# iobbq_main.net
KiCad netlist of a schematic drawn in EAGLE
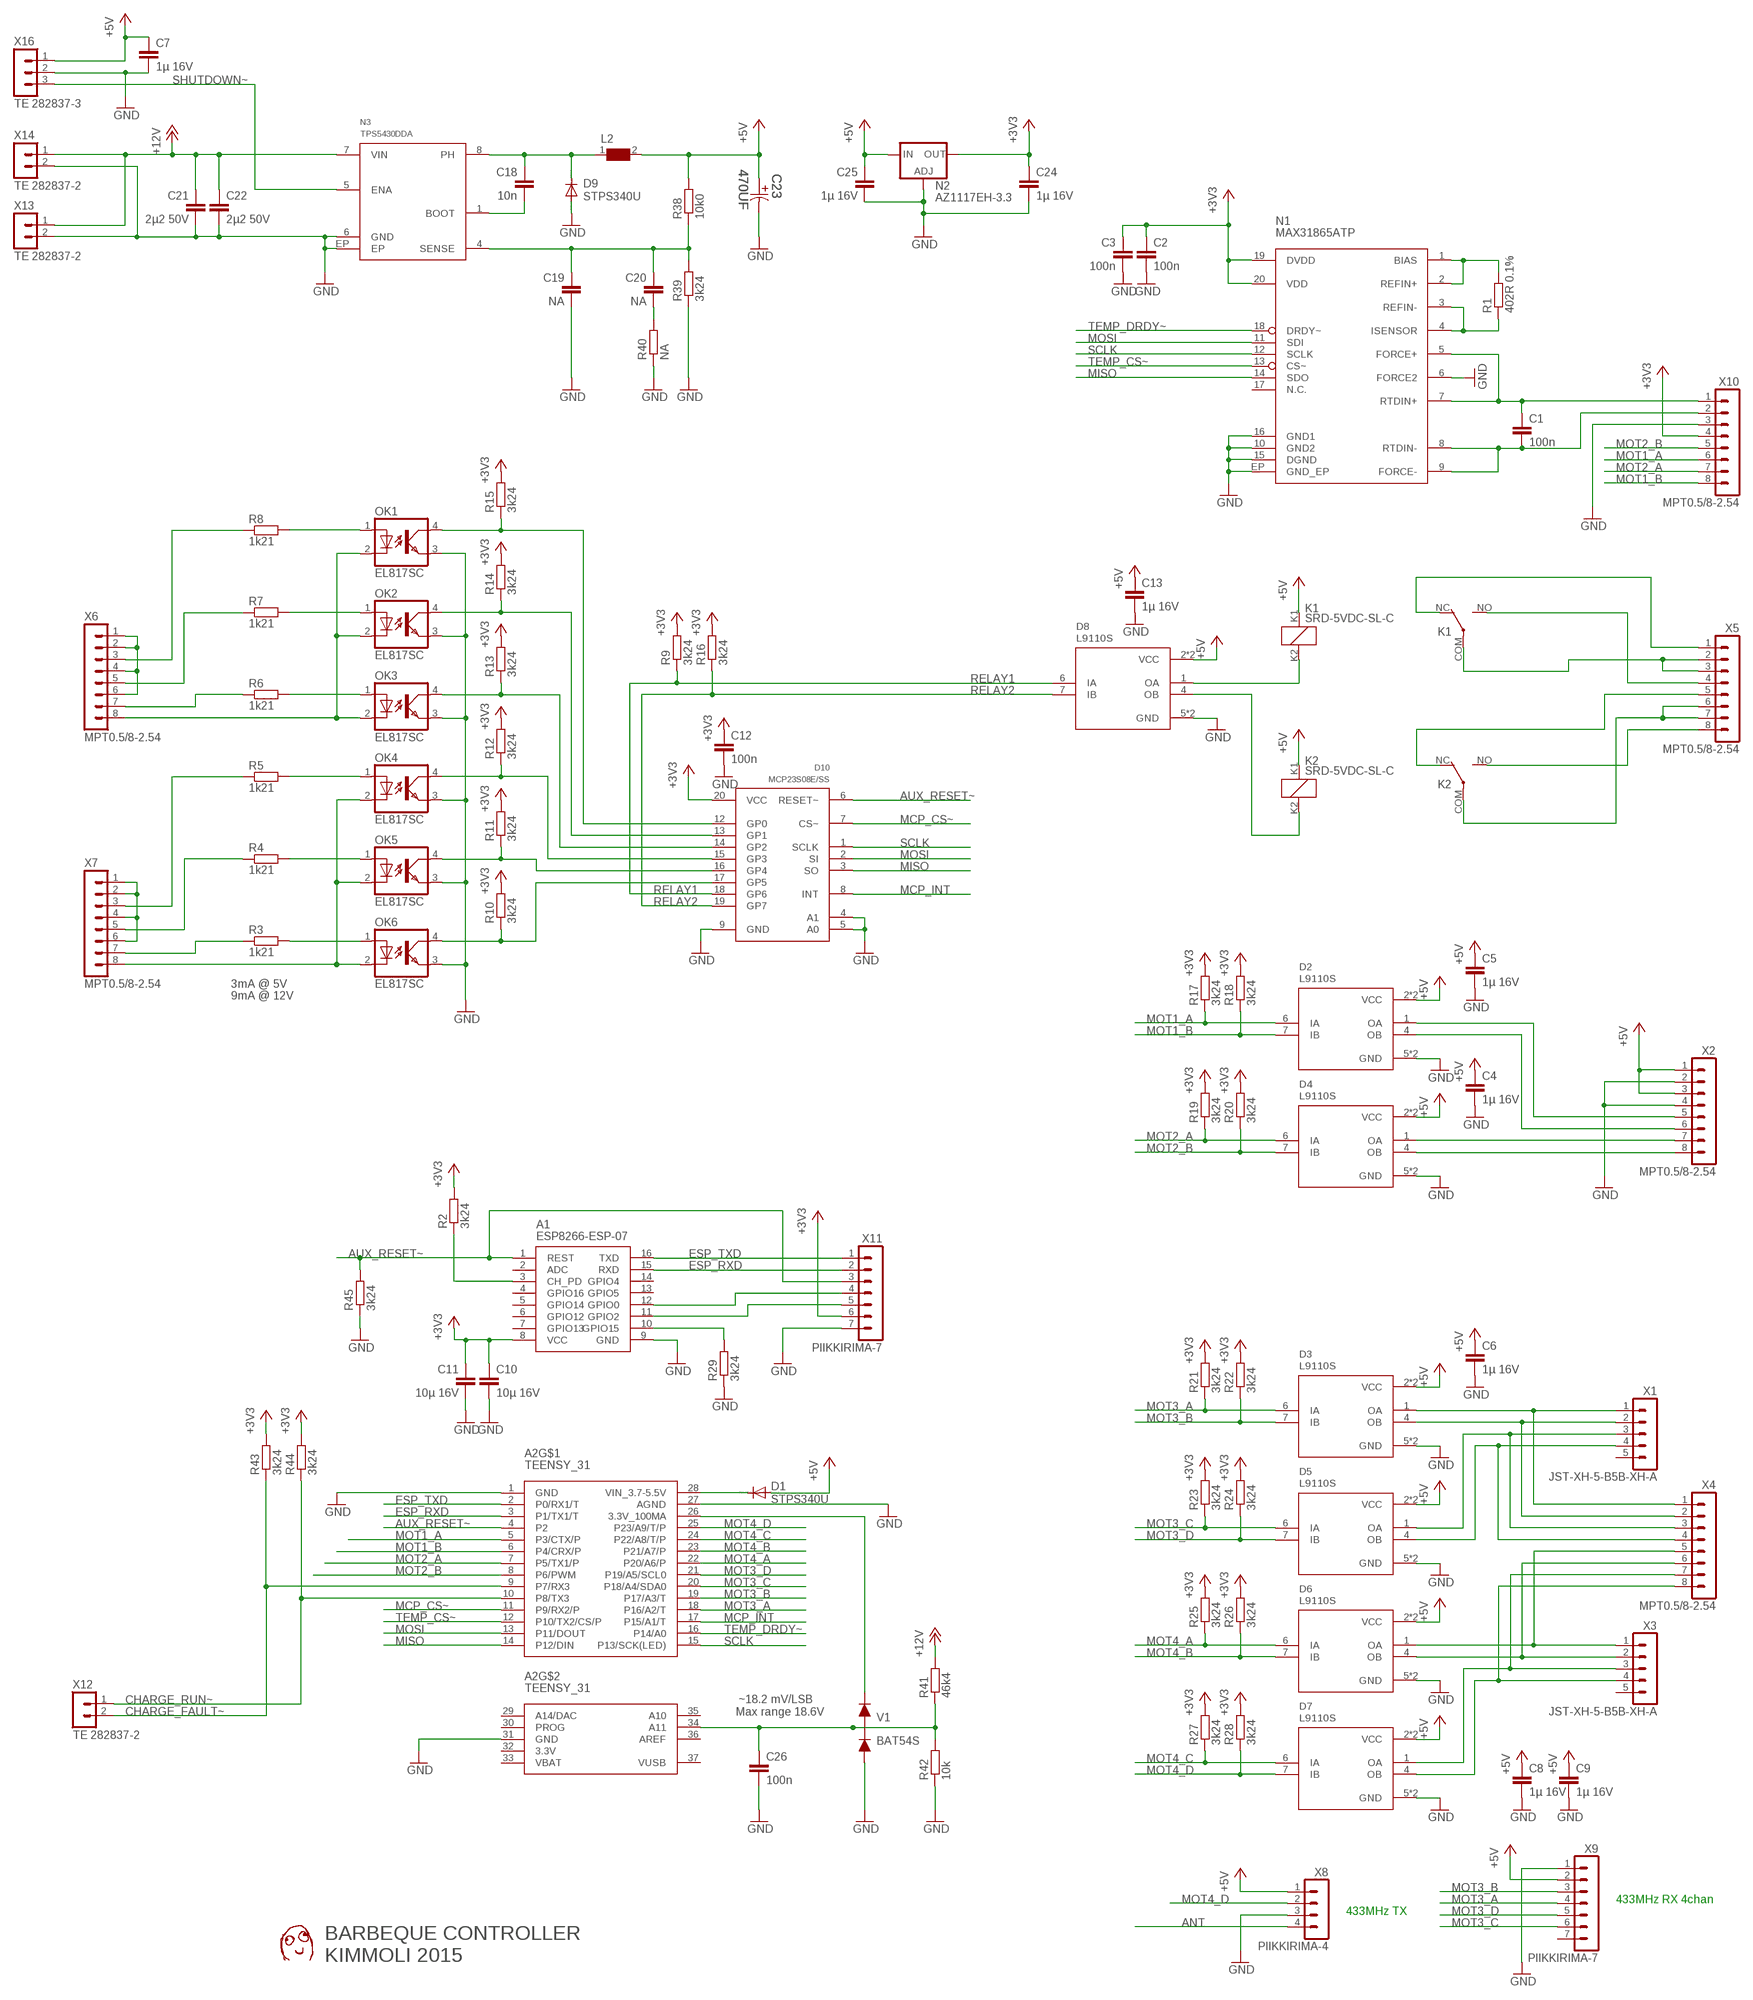
[diagram p0: schematic, sheet 1]

(export (version "E")
  (design (tool "Eeschema 10.0.6"))
  (components
    (comp (ref "A1")
      (value "ESP8266-ESP-07")
      (footprint "eagle-import:ESP8266-ESP-07")
      (libsource (lib "eagle-import") (part "ESP8266-ESP-07"))
    )
    (comp (ref "A2")
      (value "TEENSY_31")
      (footprint "eagle-import:TEENSY_31_THONLY")
      (libsource (lib "eagle-import") (part "TEENSY_31"))
    )
    (comp (ref "C1")
      (value "100n")
      (footprint "eagle-import:C0603")
      (libsource (lib "eagle-import") (part "CAP0603"))
    )
    (comp (ref "C2")
      (value "100n")
      (footprint "eagle-import:C0603")
      (libsource (lib "eagle-import") (part "CAP0603"))
    )
    (comp (ref "C3")
      (value "100n")
      (footprint "eagle-import:C0603")
      (libsource (lib "eagle-import") (part "CAP0603"))
    )
    (comp (ref "C4")
      (value "1µ 16V")
      (footprint "eagle-import:C0805")
      (libsource (lib "eagle-import") (part "CAP0805"))
    )
    (comp (ref "C5")
      (value "1µ 16V")
      (footprint "eagle-import:C0805")
      (libsource (lib "eagle-import") (part "CAP0805"))
    )
    (comp (ref "C6")
      (value "1µ 16V")
      (footprint "eagle-import:C0805")
      (libsource (lib "eagle-import") (part "CAP0805"))
    )
    (comp (ref "C7")
      (value "1µ 16V")
      (footprint "eagle-import:C0805")
      (libsource (lib "eagle-import") (part "CAP0805"))
    )
    (comp (ref "C8")
      (value "1µ 16V")
      (footprint "eagle-import:C0805")
      (libsource (lib "eagle-import") (part "CAP0805"))
    )
    (comp (ref "C9")
      (value "1µ 16V")
      (footprint "eagle-import:C0805")
      (libsource (lib "eagle-import") (part "CAP0805"))
    )
    (comp (ref "C10")
      (value "10µ 16V")
      (footprint "eagle-import:C0805")
      (libsource (lib "eagle-import") (part "CAP0805"))
    )
    (comp (ref "C11")
      (value "10µ 16V")
      (footprint "eagle-import:C0805")
      (libsource (lib "eagle-import") (part "CAP0805"))
    )
    (comp (ref "C12")
      (value "100n")
      (footprint "eagle-import:C0603")
      (libsource (lib "eagle-import") (part "CAP0603"))
    )
    (comp (ref "C13")
      (value "1µ 16V")
      (footprint "eagle-import:C0805")
      (libsource (lib "eagle-import") (part "CAP0805"))
    )
    (comp (ref "C18")
      (value "10n")
      (footprint "eagle-import:C0805")
      (libsource (lib "eagle-import") (part "CAP0805"))
    )
    (comp (ref "C19")
      (value "NA")
      (footprint "eagle-import:C0603")
      (libsource (lib "eagle-import") (part "CAP0603"))
    )
    (comp (ref "C20")
      (value "NA")
      (footprint "eagle-import:C0603")
      (libsource (lib "eagle-import") (part "CAP0603"))
    )
    (comp (ref "C21")
      (value "2µ2 50V")
      (footprint "eagle-import:C0805")
      (libsource (lib "eagle-import") (part "CAP0805"))
    )
    (comp (ref "C22")
      (value "2µ2 50V")
      (footprint "eagle-import:C0805")
      (libsource (lib "eagle-import") (part "CAP0805"))
    )
    (comp (ref "C23")
      (value "470UF")
      (footprint "eagle-import:CAPAE1350X1400N")
      (fields (field (name "MPN") "EEVFK1V471Q") (field (name "TOLERANCE") "±20 %"))
      (libsource (lib "eagle-import") (part "EEV--CASE-H13FK1V471Q"))
    )
    (comp (ref "C24")
      (value "1µ 16V")
      (footprint "eagle-import:C0805")
      (libsource (lib "eagle-import") (part "CAP0805"))
    )
    (comp (ref "C25")
      (value "1µ 16V")
      (footprint "eagle-import:C0805")
      (libsource (lib "eagle-import") (part "CAP0805"))
    )
    (comp (ref "C26")
      (value "100n")
      (footprint "eagle-import:C0603")
      (libsource (lib "eagle-import") (part "CAP0603"))
    )
    (comp (ref "D1")
      (value "STPS340U")
      (footprint "eagle-import:SMB")
      (libsource (lib "eagle-import") (part "DIODE-SMB"))
    )
    (comp (ref "D2")
      (value "L9110S")
      (footprint "eagle-import:SOIC8-N_MC")
      (libsource (lib "eagle-import") (part "L9110S"))
    )
    (comp (ref "D3")
      (value "L9110S")
      (footprint "eagle-import:SOIC8-N_MC")
      (libsource (lib "eagle-import") (part "L9110S"))
    )
    (comp (ref "D4")
      (value "L9110S")
      (footprint "eagle-import:SOIC8-N_MC")
      (libsource (lib "eagle-import") (part "L9110S"))
    )
    (comp (ref "D5")
      (value "L9110S")
      (footprint "eagle-import:SOIC8-N_MC")
      (libsource (lib "eagle-import") (part "L9110S"))
    )
    (comp (ref "D6")
      (value "L9110S")
      (footprint "eagle-import:SOIC8-N_MC")
      (libsource (lib "eagle-import") (part "L9110S"))
    )
    (comp (ref "D7")
      (value "L9110S")
      (footprint "eagle-import:SOIC8-N_MC")
      (libsource (lib "eagle-import") (part "L9110S"))
    )
    (comp (ref "D8")
      (value "L9110S")
      (footprint "eagle-import:SOIC8-N_MC")
      (libsource (lib "eagle-import") (part "L9110S"))
    )
    (comp (ref "D9")
      (value "STPS340U")
      (footprint "eagle-import:SMB")
      (libsource (lib "eagle-import") (part "DIODE-SMB"))
    )
    (comp (ref "D10")
      (value "MCP23S08E/SS")
      (footprint "eagle-import:SSOP-20")
      (libsource (lib "eagle-import") (part "MCP23S08E/SS"))
    )
    (comp (ref "K1")
      (value "SRD-5VDC-SL-C")
      (footprint "eagle-import:SRD-SL-C")
      (libsource (lib "eagle-import") (part "SRD-5VDC-SL-C"))
    )
    (comp (ref "K2")
      (value "SRD-5VDC-SL-C")
      (footprint "eagle-import:SRD-SL-C")
      (libsource (lib "eagle-import") (part "SRD-5VDC-SL-C"))
    )
    (comp (ref "L2")
      (value "WE-PD-7447709220_1260/1245/1280/1210")
      (footprint "eagle-import:WE-PD_1260_1245_1280_1210")
      (fields (field (name "MPN") "7447709220"))
      (libsource (lib "eagle-import") (part "WE-PD_1260/1245/1280/1210-7447709220"))
    )
    (comp (ref "N1")
      (value "MAX31865ATP")
      (footprint "eagle-import:TQFN-20")
      (libsource (lib "eagle-import") (part "MAX31865ATP"))
    )
    (comp (ref "N2")
      (value "AZ1117EH-3.3")
      (footprint "eagle-import:SOT223")
      (libsource (lib "eagle-import") (part "LD117A?S33TR"))
    )
    (comp (ref "N3")
      (value "TPS5430DDA")
      (footprint "eagle-import:SOIC8-N-EP")
      (libsource (lib "eagle-import") (part "TPS5430DDA"))
    )
    (comp (ref "OK1")
      (value "EL817SC")
      (footprint "eagle-import:SMD4-7")
      (fields (field (name "MF") "VISHAY/TELEFUNKEN") (field (name "MPN") "SFH6186-2"))
      (libsource (lib "eagle-import") (part "SFH618?6-2"))
    )
    (comp (ref "OK2")
      (value "EL817SC")
      (footprint "eagle-import:SMD4-7")
      (fields (field (name "MF") "VISHAY/TELEFUNKEN") (field (name "MPN") "SFH6186-2"))
      (libsource (lib "eagle-import") (part "SFH618?6-2"))
    )
    (comp (ref "OK3")
      (value "EL817SC")
      (footprint "eagle-import:SMD4-7")
      (fields (field (name "MF") "VISHAY/TELEFUNKEN") (field (name "MPN") "SFH6186-2"))
      (libsource (lib "eagle-import") (part "SFH618?6-2"))
    )
    (comp (ref "OK4")
      (value "EL817SC")
      (footprint "eagle-import:SMD4-7")
      (fields (field (name "MF") "VISHAY/TELEFUNKEN") (field (name "MPN") "SFH6186-2"))
      (libsource (lib "eagle-import") (part "SFH618?6-2"))
    )
    (comp (ref "OK5")
      (value "EL817SC")
      (footprint "eagle-import:SMD4-7")
      (fields (field (name "MF") "VISHAY/TELEFUNKEN") (field (name "MPN") "SFH6186-2"))
      (libsource (lib "eagle-import") (part "SFH618?6-2"))
    )
    (comp (ref "OK6")
      (value "EL817SC")
      (footprint "eagle-import:SMD4-7")
      (fields (field (name "MF") "VISHAY/TELEFUNKEN") (field (name "MPN") "SFH6186-2"))
      (libsource (lib "eagle-import") (part "SFH618?6-2"))
    )
    (comp (ref "R1")
      (value "402R 0.1%")
      (footprint "eagle-import:R0603")
      (libsource (lib "eagle-import") (part "RES0603"))
    )
    (comp (ref "R2")
      (value "3k24")
      (footprint "eagle-import:R0603")
      (libsource (lib "eagle-import") (part "RES0603"))
    )
    (comp (ref "R3")
      (value "1k21")
      (footprint "eagle-import:R0805")
      (libsource (lib "eagle-import") (part "RES0805"))
    )
    (comp (ref "R4")
      (value "1k21")
      (footprint "eagle-import:R0805")
      (libsource (lib "eagle-import") (part "RES0805"))
    )
    (comp (ref "R5")
      (value "1k21")
      (footprint "eagle-import:R0805")
      (libsource (lib "eagle-import") (part "RES0805"))
    )
    (comp (ref "R6")
      (value "1k21")
      (footprint "eagle-import:R0805")
      (libsource (lib "eagle-import") (part "RES0805"))
    )
    (comp (ref "R7")
      (value "1k21")
      (footprint "eagle-import:R0805")
      (libsource (lib "eagle-import") (part "RES0805"))
    )
    (comp (ref "R8")
      (value "1k21")
      (footprint "eagle-import:R0805")
      (libsource (lib "eagle-import") (part "RES0805"))
    )
    (comp (ref "R9")
      (value "3k24")
      (footprint "eagle-import:R0603")
      (libsource (lib "eagle-import") (part "RES0603"))
    )
    (comp (ref "R10")
      (value "3k24")
      (footprint "eagle-import:R0603")
      (libsource (lib "eagle-import") (part "RES0603"))
    )
    (comp (ref "R11")
      (value "3k24")
      (footprint "eagle-import:R0603")
      (libsource (lib "eagle-import") (part "RES0603"))
    )
    (comp (ref "R12")
      (value "3k24")
      (footprint "eagle-import:R0603")
      (libsource (lib "eagle-import") (part "RES0603"))
    )
    (comp (ref "R13")
      (value "3k24")
      (footprint "eagle-import:R0603")
      (libsource (lib "eagle-import") (part "RES0603"))
    )
    (comp (ref "R14")
      (value "3k24")
      (footprint "eagle-import:R0603")
      (libsource (lib "eagle-import") (part "RES0603"))
    )
    (comp (ref "R15")
      (value "3k24")
      (footprint "eagle-import:R0603")
      (libsource (lib "eagle-import") (part "RES0603"))
    )
    (comp (ref "R16")
      (value "3k24")
      (footprint "eagle-import:R0603")
      (libsource (lib "eagle-import") (part "RES0603"))
    )
    (comp (ref "R17")
      (value "3k24")
      (footprint "eagle-import:R0603")
      (libsource (lib "eagle-import") (part "RES0603"))
    )
    (comp (ref "R18")
      (value "3k24")
      (footprint "eagle-import:R0603")
      (libsource (lib "eagle-import") (part "RES0603"))
    )
    (comp (ref "R19")
      (value "3k24")
      (footprint "eagle-import:R0603")
      (libsource (lib "eagle-import") (part "RES0603"))
    )
    (comp (ref "R20")
      (value "3k24")
      (footprint "eagle-import:R0603")
      (libsource (lib "eagle-import") (part "RES0603"))
    )
    (comp (ref "R21")
      (value "3k24")
      (footprint "eagle-import:R0603")
      (libsource (lib "eagle-import") (part "RES0603"))
    )
    (comp (ref "R22")
      (value "3k24")
      (footprint "eagle-import:R0603")
      (libsource (lib "eagle-import") (part "RES0603"))
    )
    (comp (ref "R23")
      (value "3k24")
      (footprint "eagle-import:R0603")
      (libsource (lib "eagle-import") (part "RES0603"))
    )
    (comp (ref "R24")
      (value "3k24")
      (footprint "eagle-import:R0603")
      (libsource (lib "eagle-import") (part "RES0603"))
    )
    (comp (ref "R25")
      (value "3k24")
      (footprint "eagle-import:R0603")
      (libsource (lib "eagle-import") (part "RES0603"))
    )
    (comp (ref "R26")
      (value "3k24")
      (footprint "eagle-import:R0603")
      (libsource (lib "eagle-import") (part "RES0603"))
    )
    (comp (ref "R27")
      (value "3k24")
      (footprint "eagle-import:R0603")
      (libsource (lib "eagle-import") (part "RES0603"))
    )
    (comp (ref "R28")
      (value "3k24")
      (footprint "eagle-import:R0603")
      (libsource (lib "eagle-import") (part "RES0603"))
    )
    (comp (ref "R29")
      (value "3k24")
      (footprint "eagle-import:R0603")
      (libsource (lib "eagle-import") (part "RES0603"))
    )
    (comp (ref "R38")
      (value "10k0")
      (footprint "eagle-import:R0603")
      (libsource (lib "eagle-import") (part "RES0603"))
    )
    (comp (ref "R39")
      (value "3k24")
      (footprint "eagle-import:R0603")
      (libsource (lib "eagle-import") (part "RES0603"))
    )
    (comp (ref "R40")
      (value "NA")
      (footprint "eagle-import:R0603")
      (libsource (lib "eagle-import") (part "RES0603"))
    )
    (comp (ref "R41")
      (value "46k4")
      (footprint "eagle-import:R0603")
      (libsource (lib "eagle-import") (part "RES0603"))
    )
    (comp (ref "R42")
      (value "10k")
      (footprint "eagle-import:R0603")
      (libsource (lib "eagle-import") (part "RES0603"))
    )
    (comp (ref "R43")
      (value "3k24")
      (footprint "eagle-import:R0603")
      (libsource (lib "eagle-import") (part "RES0603"))
    )
    (comp (ref "R44")
      (value "3k24")
      (footprint "eagle-import:R0603")
      (libsource (lib "eagle-import") (part "RES0603"))
    )
    (comp (ref "R45")
      (value "3k24")
      (footprint "eagle-import:R0603")
      (libsource (lib "eagle-import") (part "RES0603"))
    )
    (comp (ref "U$3")
      (value "DAFUG")
      (footprint "eagle-import:DAFUG")
      (libsource (lib "eagle-import") (part "DAFUG"))
    )
    (comp (ref "V1")
      (value "BAT54S")
      (footprint "eagle-import:SOT23")
      (libsource (lib "eagle-import") (part "BAT54S"))
    )
    (comp (ref "X1")
      (value "JST-XH-5-B5B-XH-A")
      (footprint "eagle-import:JST-XH-5")
      (libsource (lib "eagle-import") (part "JST-XH-5-B5B-XH-A"))
    )
    (comp (ref "X2")
      (value "MPT0.5/8-2.54")
      (footprint "eagle-import:MPT0.5_8-2.54")
      (libsource (lib "eagle-import") (part "MPT0.5/8-2.54"))
    )
    (comp (ref "X3")
      (value "JST-XH-5-B5B-XH-A")
      (footprint "eagle-import:JST-XH-5")
      (libsource (lib "eagle-import") (part "JST-XH-5-B5B-XH-A"))
    )
    (comp (ref "X4")
      (value "MPT0.5/8-2.54")
      (footprint "eagle-import:MPT0.5_8-2.54")
      (libsource (lib "eagle-import") (part "MPT0.5/8-2.54"))
    )
    (comp (ref "X5")
      (value "MPT0.5/8-2.54")
      (footprint "eagle-import:MPT0.5_8-2.54")
      (libsource (lib "eagle-import") (part "MPT0.5/8-2.54"))
    )
    (comp (ref "X6")
      (value "MPT0.5/8-2.54")
      (footprint "eagle-import:MPT0.5_8-2.54")
      (libsource (lib "eagle-import") (part "MPT0.5/8-2.54"))
    )
    (comp (ref "X7")
      (value "MPT0.5/8-2.54")
      (footprint "eagle-import:MPT0.5_8-2.54")
      (libsource (lib "eagle-import") (part "MPT0.5/8-2.54"))
    )
    (comp (ref "X8")
      (value "PIIKKIRIMA-4")
      (footprint "eagle-import:PIIKKIRIMA-4")
      (libsource (lib "eagle-import") (part "PIIKKIRIMA-4"))
    )
    (comp (ref "X9")
      (value "PIIKKIRIMA-7")
      (footprint "eagle-import:PIIKKIRIMA-7")
      (libsource (lib "eagle-import") (part "PIIKKIRIMA-7"))
    )
    (comp (ref "X10")
      (value "MPT0.5/8-2.54")
      (footprint "eagle-import:MPT0.5_8-2.54")
      (libsource (lib "eagle-import") (part "MPT0.5/8-2.54"))
    )
    (comp (ref "X11")
      (value "PIIKKIRIMA-7")
      (footprint "eagle-import:PIIKKIRIMA-7")
      (libsource (lib "eagle-import") (part "PIIKKIRIMA-7"))
    )
    (comp (ref "X12")
      (value "TE 282837-2")
      (footprint "eagle-import:TE_RUUVILIITIN2")
      (libsource (lib "eagle-import") (part "TE_RUUVILIITIN2"))
    )
    (comp (ref "X13")
      (value "TE 282837-2")
      (footprint "eagle-import:TE_RUUVILIITIN2")
      (libsource (lib "eagle-import") (part "TE_RUUVILIITIN2"))
    )
    (comp (ref "X14")
      (value "TE 282837-2")
      (footprint "eagle-import:TE_RUUVILIITIN2")
      (libsource (lib "eagle-import") (part "TE_RUUVILIITIN2"))
    )
    (comp (ref "X16")
      (value "TE 282837-3")
      (footprint "eagle-import:TE_RUUVILIITIN3")
      (libsource (lib "eagle-import") (part "TE_RUUVILIITIN3"))
    )
  )
  (nets
    (net (code "1") (name "+3V3") (class "Default")
      (node (ref "A1") (pin "8") (pinfunction "VCC_8") (pintype "bidirectional"))
      (node (ref "C10") (pin "1") (pinfunction "1_1") (pintype "passive"))
      (node (ref "C11") (pin "1") (pinfunction "1_1") (pintype "passive"))
      (node (ref "C12") (pin "1") (pinfunction "1_1") (pintype "passive"))
      (node (ref "C2") (pin "1") (pinfunction "1_1") (pintype "passive"))
      (node (ref "C24") (pin "1") (pinfunction "1_1") (pintype "passive"))
      (node (ref "C3") (pin "1") (pinfunction "1_1") (pintype "passive"))
      (node (ref "D10") (pin "20") (pinfunction "VCC_20") (pintype "bidirectional"))
      (node (ref "N1") (pin "19") (pinfunction "DVDD_19") (pintype "bidirectional"))
      (node (ref "N1") (pin "20") (pinfunction "VDD_20") (pintype "bidirectional"))
      (node (ref "N2") (pin "4") (pinfunction "OUT_4") (pintype "passive"))
      (node (ref "R10") (pin "2") (pinfunction "2_2") (pintype "passive"))
      (node (ref "R11") (pin "2") (pinfunction "2_2") (pintype "passive"))
      (node (ref "R12") (pin "2") (pinfunction "2_2") (pintype "passive"))
      (node (ref "R13") (pin "2") (pinfunction "2_2") (pintype "passive"))
      (node (ref "R14") (pin "2") (pinfunction "2_2") (pintype "passive"))
      (node (ref "R15") (pin "2") (pinfunction "2_2") (pintype "passive"))
      (node (ref "R16") (pin "2") (pinfunction "2_2") (pintype "passive"))
      (node (ref "R17") (pin "2") (pinfunction "2_2") (pintype "passive"))
      (node (ref "R18") (pin "2") (pinfunction "2_2") (pintype "passive"))
      (node (ref "R19") (pin "2") (pinfunction "2_2") (pintype "passive"))
      (node (ref "R2") (pin "2") (pinfunction "2_2") (pintype "passive"))
      (node (ref "R20") (pin "2") (pinfunction "2_2") (pintype "passive"))
      (node (ref "R21") (pin "2") (pinfunction "2_2") (pintype "passive"))
      (node (ref "R22") (pin "2") (pinfunction "2_2") (pintype "passive"))
      (node (ref "R23") (pin "2") (pinfunction "2_2") (pintype "passive"))
      (node (ref "R24") (pin "2") (pinfunction "2_2") (pintype "passive"))
      (node (ref "R25") (pin "2") (pinfunction "2_2") (pintype "passive"))
      (node (ref "R26") (pin "2") (pinfunction "2_2") (pintype "passive"))
      (node (ref "R27") (pin "2") (pinfunction "2_2") (pintype "passive"))
      (node (ref "R28") (pin "2") (pinfunction "2_2") (pintype "passive"))
      (node (ref "R43") (pin "2") (pinfunction "2_2") (pintype "passive"))
      (node (ref "R44") (pin "2") (pinfunction "2_2") (pintype "passive"))
      (node (ref "R9") (pin "2") (pinfunction "2_2") (pintype "passive"))
      (node (ref "X10") (pin "4") (pinfunction "4_4") (pintype "passive"))
      (node (ref "X11") (pin "6") (pinfunction "6_6") (pintype "passive"))
    )
    (net (code "2") (name "+5V") (class "Default")
      (node (ref "C13") (pin "1") (pinfunction "1_1") (pintype "passive"))
      (node (ref "C23") (pin "1") (pinfunction "1_1") (pintype "passive"))
      (node (ref "C25") (pin "1") (pinfunction "1_1") (pintype "passive"))
      (node (ref "C4") (pin "1") (pinfunction "1_1") (pintype "passive"))
      (node (ref "C5") (pin "1") (pinfunction "1_1") (pintype "passive"))
      (node (ref "C6") (pin "1") (pinfunction "1_1") (pintype "passive"))
      (node (ref "C7") (pin "1") (pinfunction "1_1") (pintype "passive"))
      (node (ref "C8") (pin "1") (pinfunction "1_1") (pintype "passive"))
      (node (ref "C9") (pin "1") (pinfunction "1_1") (pintype "passive"))
      (node (ref "D1") (pin "A") (pinfunction "A_A") (pintype "passive"))
      (node (ref "D2") (pin "2") (pinfunction "VCC_2") (pintype "bidirectional"))
      (node (ref "D2") (pin "3") (pinfunction "VCC_3") (pintype "bidirectional"))
      (node (ref "D3") (pin "2") (pinfunction "VCC_2") (pintype "bidirectional"))
      (node (ref "D3") (pin "3") (pinfunction "VCC_3") (pintype "bidirectional"))
      (node (ref "D4") (pin "2") (pinfunction "VCC_2") (pintype "bidirectional"))
      (node (ref "D4") (pin "3") (pinfunction "VCC_3") (pintype "bidirectional"))
      (node (ref "D5") (pin "2") (pinfunction "VCC_2") (pintype "bidirectional"))
      (node (ref "D5") (pin "3") (pinfunction "VCC_3") (pintype "bidirectional"))
      (node (ref "D6") (pin "2") (pinfunction "VCC_2") (pintype "bidirectional"))
      (node (ref "D6") (pin "3") (pinfunction "VCC_3") (pintype "bidirectional"))
      (node (ref "D7") (pin "2") (pinfunction "VCC_2") (pintype "bidirectional"))
      (node (ref "D7") (pin "3") (pinfunction "VCC_3") (pintype "bidirectional"))
      (node (ref "D8") (pin "2") (pinfunction "VCC_2") (pintype "bidirectional"))
      (node (ref "D8") (pin "3") (pinfunction "VCC_3") (pintype "bidirectional"))
      (node (ref "K1") (pin "K1") (pinfunction "1_K1") (pintype "passive"))
      (node (ref "K2") (pin "K1") (pinfunction "1_K1") (pintype "passive"))
      (node (ref "L2") (pin "2") (pinfunction "2_2") (pintype "passive"))
      (node (ref "N2") (pin "3") (pinfunction "IN_3") (pintype "input"))
      (node (ref "R38") (pin "2") (pinfunction "2_2") (pintype "passive"))
      (node (ref "X16") (pin "1") (pinfunction "1_1") (pintype "passive"))
      (node (ref "X2") (pin "1") (pinfunction "1_1") (pintype "passive"))
      (node (ref "X2") (pin "3") (pinfunction "3_3") (pintype "passive"))
      (node (ref "X8") (pin "1") (pinfunction "1_1") (pintype "passive"))
      (node (ref "X9") (pin "2") (pinfunction "2_2") (pintype "passive"))
    )
    (net (code "3") (name "+12V") (class "Default")
      (node (ref "C21") (pin "1") (pinfunction "1_1") (pintype "passive"))
      (node (ref "C22") (pin "1") (pinfunction "1_1") (pintype "passive"))
      (node (ref "N3") (pin "7") (pinfunction "VIN_7") (pintype "bidirectional"))
      (node (ref "R41") (pin "2") (pinfunction "2_2") (pintype "passive"))
      (node (ref "X13") (pin "1") (pinfunction "1_1") (pintype "passive"))
      (node (ref "X14") (pin "1") (pinfunction "1_1") (pintype "passive"))
    )
    (net (code "4") (name "/ANT") (class "Default")
      (node (ref "X8") (pin "4") (pinfunction "4_4") (pintype "passive"))
    )
    (net (code "5") (name "/AUX_RESET~{}") (class "Default")
      (node (ref "A1") (pin "1") (pinfunction "REST_1") (pintype "bidirectional"))
      (node (ref "A2") (pin "4") (pinfunction "P2_4") (pintype "bidirectional"))
      (node (ref "D10") (pin "6") (pinfunction "RESET~{}_6") (pintype "bidirectional"))
      (node (ref "R45") (pin "2") (pinfunction "2_2") (pintype "passive"))
      (node (ref "X11") (pin "3") (pinfunction "3_3") (pintype "passive"))
    )
    (net (code "6") (name "/CHARGE_FAULT~{}") (class "Default")
      (node (ref "A2") (pin "9") (pinfunction "P7/RX3_9") (pintype "bidirectional"))
      (node (ref "R43") (pin "1") (pinfunction "1_1") (pintype "passive"))
      (node (ref "X12") (pin "2") (pinfunction "2_2") (pintype "passive"))
    )
    (net (code "7") (name "/CHARGE_RUN~{}") (class "Default")
      (node (ref "A2") (pin "10") (pinfunction "P8/TX3_10") (pintype "bidirectional"))
      (node (ref "R44") (pin "1") (pinfunction "1_1") (pintype "passive"))
      (node (ref "X12") (pin "1") (pinfunction "1_1") (pintype "passive"))
    )
    (net (code "8") (name "/ESP_RXD") (class "Default")
      (node (ref "A1") (pin "15") (pinfunction "RXD_15") (pintype "bidirectional"))
      (node (ref "A2") (pin "3") (pinfunction "P1/TX1/T_3") (pintype "bidirectional"))
      (node (ref "X11") (pin "2") (pinfunction "2_2") (pintype "passive"))
    )
    (net (code "9") (name "/ESP_TXD") (class "Default")
      (node (ref "A1") (pin "16") (pinfunction "TXD_16") (pintype "bidirectional"))
      (node (ref "A2") (pin "2") (pinfunction "P0/RX1/T_2") (pintype "bidirectional"))
      (node (ref "X11") (pin "1") (pinfunction "1_1") (pintype "passive"))
    )
    (net (code "10") (name "/MCP_CS~{}") (class "Default")
      (node (ref "A2") (pin "11") (pinfunction "P9/RX2/P_11") (pintype "bidirectional"))
      (node (ref "D10") (pin "7") (pinfunction "CS~{}_7") (pintype "bidirectional"))
    )
    (net (code "11") (name "/MCP_INT") (class "Default")
      (node (ref "A2") (pin "17") (pinfunction "P15/A1/T_17") (pintype "bidirectional"))
      (node (ref "D10") (pin "8") (pinfunction "INT_8") (pintype "bidirectional"))
    )
    (net (code "12") (name "/MISO") (class "Default")
      (node (ref "A2") (pin "14") (pinfunction "P12/DIN_14") (pintype "bidirectional"))
      (node (ref "D10") (pin "3") (pinfunction "SO_3") (pintype "bidirectional"))
      (node (ref "N1") (pin "14") (pinfunction "SDO_14") (pintype "bidirectional"))
    )
    (net (code "13") (name "/MOSI") (class "Default")
      (node (ref "A2") (pin "13") (pinfunction "P11/DOUT_13") (pintype "bidirectional"))
      (node (ref "D10") (pin "2") (pinfunction "SI_2") (pintype "bidirectional"))
      (node (ref "N1") (pin "11") (pinfunction "SDI_11") (pintype "bidirectional"))
    )
    (net (code "14") (name "/MOT1_A") (class "Default")
      (node (ref "A2") (pin "5") (pinfunction "P3/CTX/P_5") (pintype "bidirectional"))
      (node (ref "D2") (pin "6") (pinfunction "IA_6") (pintype "bidirectional"))
      (node (ref "R17") (pin "1") (pinfunction "1_1") (pintype "passive"))
      (node (ref "X10") (pin "6") (pinfunction "6_6") (pintype "passive"))
    )
    (net (code "15") (name "/MOT1_B") (class "Default")
      (node (ref "A2") (pin "6") (pinfunction "P4/CRX/P_6") (pintype "bidirectional"))
      (node (ref "D2") (pin "7") (pinfunction "IB_7") (pintype "bidirectional"))
      (node (ref "R18") (pin "1") (pinfunction "1_1") (pintype "passive"))
      (node (ref "X10") (pin "8") (pinfunction "8_8") (pintype "passive"))
    )
    (net (code "16") (name "/MOT2_A") (class "Default")
      (node (ref "A2") (pin "7") (pinfunction "P5/TX1/P_7") (pintype "bidirectional"))
      (node (ref "D4") (pin "6") (pinfunction "IA_6") (pintype "bidirectional"))
      (node (ref "R19") (pin "1") (pinfunction "1_1") (pintype "passive"))
      (node (ref "X10") (pin "7") (pinfunction "7_7") (pintype "passive"))
    )
    (net (code "17") (name "/MOT2_B") (class "Default")
      (node (ref "A2") (pin "8") (pinfunction "P6/PWM_8") (pintype "bidirectional"))
      (node (ref "D4") (pin "7") (pinfunction "IB_7") (pintype "bidirectional"))
      (node (ref "R20") (pin "1") (pinfunction "1_1") (pintype "passive"))
      (node (ref "X10") (pin "5") (pinfunction "5_5") (pintype "passive"))
    )
    (net (code "18") (name "/MOT3_A") (class "Default")
      (node (ref "A2") (pin "18") (pinfunction "P16/A2/T_18") (pintype "bidirectional"))
      (node (ref "D3") (pin "6") (pinfunction "IA_6") (pintype "bidirectional"))
      (node (ref "R21") (pin "1") (pinfunction "1_1") (pintype "passive"))
      (node (ref "X9") (pin "4") (pinfunction "4_4") (pintype "passive"))
    )
    (net (code "19") (name "/MOT3_B") (class "Default")
      (node (ref "A2") (pin "19") (pinfunction "P17/A3/T_19") (pintype "bidirectional"))
      (node (ref "D3") (pin "7") (pinfunction "IB_7") (pintype "bidirectional"))
      (node (ref "R22") (pin "1") (pinfunction "1_1") (pintype "passive"))
      (node (ref "X9") (pin "3") (pinfunction "3_3") (pintype "passive"))
    )
    (net (code "20") (name "/MOT3_C") (class "Default")
      (node (ref "A2") (pin "20") (pinfunction "P18/A4/SDA0_20") (pintype "bidirectional"))
      (node (ref "D5") (pin "6") (pinfunction "IA_6") (pintype "bidirectional"))
      (node (ref "R23") (pin "1") (pinfunction "1_1") (pintype "passive"))
      (node (ref "X9") (pin "6") (pinfunction "6_6") (pintype "passive"))
    )
    (net (code "21") (name "/MOT3_D") (class "Default")
      (node (ref "A2") (pin "21") (pinfunction "P19/A5/SCL0_21") (pintype "bidirectional"))
      (node (ref "D5") (pin "7") (pinfunction "IB_7") (pintype "bidirectional"))
      (node (ref "R24") (pin "1") (pinfunction "1_1") (pintype "passive"))
      (node (ref "X9") (pin "5") (pinfunction "5_5") (pintype "passive"))
    )
    (net (code "22") (name "/MOT4_A") (class "Default")
      (node (ref "A2") (pin "22") (pinfunction "P20/A6/P_22") (pintype "bidirectional"))
      (node (ref "D6") (pin "6") (pinfunction "IA_6") (pintype "bidirectional"))
      (node (ref "R25") (pin "1") (pinfunction "1_1") (pintype "passive"))
    )
    (net (code "23") (name "/MOT4_B") (class "Default")
      (node (ref "A2") (pin "23") (pinfunction "P21/A7/P_23") (pintype "bidirectional"))
      (node (ref "D6") (pin "7") (pinfunction "IB_7") (pintype "bidirectional"))
      (node (ref "R26") (pin "1") (pinfunction "1_1") (pintype "passive"))
    )
    (net (code "24") (name "/MOT4_C") (class "Default")
      (node (ref "A2") (pin "24") (pinfunction "P22/A8/T/P_24") (pintype "bidirectional"))
      (node (ref "D7") (pin "6") (pinfunction "IA_6") (pintype "bidirectional"))
      (node (ref "R27") (pin "1") (pinfunction "1_1") (pintype "passive"))
    )
    (net (code "25") (name "/MOT4_D") (class "Default")
      (node (ref "A2") (pin "25") (pinfunction "P23/A9/T/P_25") (pintype "bidirectional"))
      (node (ref "D7") (pin "7") (pinfunction "IB_7") (pintype "bidirectional"))
      (node (ref "R28") (pin "1") (pinfunction "1_1") (pintype "passive"))
      (node (ref "X8") (pin "2") (pinfunction "2_2") (pintype "passive"))
    )
    (net (code "26") (name "/RELAY1") (class "Default")
      (node (ref "D10") (pin "18") (pinfunction "GP6_18") (pintype "bidirectional"))
      (node (ref "D8") (pin "6") (pinfunction "IA_6") (pintype "bidirectional"))
      (node (ref "R9") (pin "1") (pinfunction "1_1") (pintype "passive"))
    )
    (net (code "27") (name "/RELAY2") (class "Default")
      (node (ref "D10") (pin "19") (pinfunction "GP7_19") (pintype "bidirectional"))
      (node (ref "D8") (pin "7") (pinfunction "IB_7") (pintype "bidirectional"))
      (node (ref "R16") (pin "1") (pinfunction "1_1") (pintype "passive"))
    )
    (net (code "28") (name "/SCLK") (class "Default")
      (node (ref "A2") (pin "15") (pinfunction "P13/SCK(LED)_15") (pintype "bidirectional"))
      (node (ref "D10") (pin "1") (pinfunction "SCLK_1") (pintype "bidirectional"))
      (node (ref "N1") (pin "12") (pinfunction "SCLK_12") (pintype "bidirectional"))
    )
    (net (code "29") (name "/SHUTDOWN~{}") (class "Default")
      (node (ref "N3") (pin "5") (pinfunction "ENA_5") (pintype "bidirectional"))
      (node (ref "X16") (pin "3") (pinfunction "3_3") (pintype "passive"))
    )
    (net (code "30") (name "/TEMP_CS~{}") (class "Default")
      (node (ref "A2") (pin "12") (pinfunction "P10/TX2/CS/P_12") (pintype "bidirectional"))
      (node (ref "N1") (pin "13") (pinfunction "CS~{}_13") (pintype "bidirectional"))
    )
    (net (code "31") (name "/TEMP_DRDY~{}") (class "Default")
      (node (ref "A2") (pin "16") (pinfunction "P14/A0_16") (pintype "bidirectional"))
      (node (ref "N1") (pin "18") (pinfunction "DRDY~{}_18") (pintype "bidirectional"))
    )
    (net (code "32") (name "GND") (class "Default")
      (node (ref "A1") (pin "9") (pinfunction "GND_9") (pintype "bidirectional"))
      (node (ref "A2") (pin "1") (pinfunction "GND_1") (pintype "bidirectional"))
      (node (ref "A2") (pin "27") (pinfunction "AGND_27") (pintype "bidirectional"))
      (node (ref "A2") (pin "31") (pinfunction "GND_31") (pintype "bidirectional"))
      (node (ref "C10") (pin "2") (pinfunction "2_2") (pintype "passive"))
      (node (ref "C11") (pin "2") (pinfunction "2_2") (pintype "passive"))
      (node (ref "C12") (pin "2") (pinfunction "2_2") (pintype "passive"))
      (node (ref "C13") (pin "2") (pinfunction "2_2") (pintype "passive"))
      (node (ref "C19") (pin "2") (pinfunction "2_2") (pintype "passive"))
      (node (ref "C2") (pin "2") (pinfunction "2_2") (pintype "passive"))
      (node (ref "C21") (pin "2") (pinfunction "2_2") (pintype "passive"))
      (node (ref "C22") (pin "2") (pinfunction "2_2") (pintype "passive"))
      (node (ref "C23") (pin "2") (pinfunction "2_2") (pintype "passive"))
      (node (ref "C24") (pin "2") (pinfunction "2_2") (pintype "passive"))
      (node (ref "C25") (pin "2") (pinfunction "2_2") (pintype "passive"))
      (node (ref "C26") (pin "2") (pinfunction "2_2") (pintype "passive"))
      (node (ref "C3") (pin "2") (pinfunction "2_2") (pintype "passive"))
      (node (ref "C4") (pin "2") (pinfunction "2_2") (pintype "passive"))
      (node (ref "C5") (pin "2") (pinfunction "2_2") (pintype "passive"))
      (node (ref "C6") (pin "2") (pinfunction "2_2") (pintype "passive"))
      (node (ref "C7") (pin "2") (pinfunction "2_2") (pintype "passive"))
      (node (ref "C8") (pin "2") (pinfunction "2_2") (pintype "passive"))
      (node (ref "C9") (pin "2") (pinfunction "2_2") (pintype "passive"))
      (node (ref "D10") (pin "4") (pinfunction "A1_4") (pintype "bidirectional"))
      (node (ref "D10") (pin "5") (pinfunction "A0_5") (pintype "bidirectional"))
      (node (ref "D10") (pin "9") (pinfunction "GND_9") (pintype "bidirectional"))
      (node (ref "D2") (pin "5") (pinfunction "GND_5") (pintype "bidirectional"))
      (node (ref "D2") (pin "8") (pinfunction "GND_8") (pintype "bidirectional"))
      (node (ref "D3") (pin "5") (pinfunction "GND_5") (pintype "bidirectional"))
      (node (ref "D3") (pin "8") (pinfunction "GND_8") (pintype "bidirectional"))
      (node (ref "D4") (pin "5") (pinfunction "GND_5") (pintype "bidirectional"))
      (node (ref "D4") (pin "8") (pinfunction "GND_8") (pintype "bidirectional"))
      (node (ref "D5") (pin "5") (pinfunction "GND_5") (pintype "bidirectional"))
      (node (ref "D5") (pin "8") (pinfunction "GND_8") (pintype "bidirectional"))
      (node (ref "D6") (pin "5") (pinfunction "GND_5") (pintype "bidirectional"))
      (node (ref "D6") (pin "8") (pinfunction "GND_8") (pintype "bidirectional"))
      (node (ref "D7") (pin "5") (pinfunction "GND_5") (pintype "bidirectional"))
      (node (ref "D7") (pin "8") (pinfunction "GND_8") (pintype "bidirectional"))
      (node (ref "D8") (pin "5") (pinfunction "GND_5") (pintype "bidirectional"))
      (node (ref "D8") (pin "8") (pinfunction "GND_8") (pintype "bidirectional"))
      (node (ref "D9") (pin "A") (pinfunction "A_A") (pintype "passive"))
      (node (ref "N1") (pin "10") (pinfunction "GND2_10") (pintype "bidirectional"))
      (node (ref "N1") (pin "15") (pinfunction "DGND_15") (pintype "bidirectional"))
      (node (ref "N1") (pin "16") (pinfunction "GND1_16") (pintype "bidirectional"))
      (node (ref "N1") (pin "6") (pinfunction "FORCE2_6") (pintype "bidirectional"))
      (node (ref "N1") (pin "EP") (pinfunction "GND_EP_EP") (pintype "bidirectional"))
      (node (ref "N2") (pin "1") (pinfunction "ADJ_1") (pintype "input"))
      (node (ref "N3") (pin "6") (pinfunction "GND_6") (pintype "bidirectional"))
      (node (ref "N3") (pin "EP") (pinfunction "EP_EP") (pintype "bidirectional"))
      (node (ref "OK1") (pin "3") (pinfunction "EMIT_3") (pintype "passive"))
      (node (ref "OK2") (pin "3") (pinfunction "EMIT_3") (pintype "passive"))
      (node (ref "OK3") (pin "3") (pinfunction "EMIT_3") (pintype "passive"))
      (node (ref "OK4") (pin "3") (pinfunction "EMIT_3") (pintype "passive"))
      (node (ref "OK5") (pin "3") (pinfunction "EMIT_3") (pintype "passive"))
      (node (ref "OK6") (pin "3") (pinfunction "EMIT_3") (pintype "passive"))
      (node (ref "R29") (pin "1") (pinfunction "1_1") (pintype "passive"))
      (node (ref "R39") (pin "1") (pinfunction "1_1") (pintype "passive"))
      (node (ref "R40") (pin "1") (pinfunction "1_1") (pintype "passive"))
      (node (ref "R42") (pin "1") (pinfunction "1_1") (pintype "passive"))
      (node (ref "R45") (pin "1") (pinfunction "1_1") (pintype "passive"))
      (node (ref "V1") (pin "1") (pinfunction "1_1") (pintype "bidirectional"))
      (node (ref "X10") (pin "3") (pinfunction "3_3") (pintype "passive"))
      (node (ref "X11") (pin "7") (pinfunction "7_7") (pintype "passive"))
      (node (ref "X13") (pin "2") (pinfunction "2_2") (pintype "passive"))
      (node (ref "X14") (pin "2") (pinfunction "2_2") (pintype "passive"))
      (node (ref "X16") (pin "2") (pinfunction "2_2") (pintype "passive"))
      (node (ref "X2") (pin "2") (pinfunction "2_2") (pintype "passive"))
      (node (ref "X2") (pin "4") (pinfunction "4_4") (pintype "passive"))
      (node (ref "X8") (pin "3") (pinfunction "3_3") (pintype "passive"))
      (node (ref "X9") (pin "1") (pinfunction "1_1") (pintype "passive"))
    )
    (net (code "33") (name "Net-(A1-CH_PD)") (class "Default")
      (node (ref "A1") (pin "3") (pinfunction "CH_PD_3") (pintype "bidirectional"))
      (node (ref "R2") (pin "1") (pinfunction "1_1") (pintype "passive"))
    )
    (net (code "34") (name "Net-(A1-GPIO0)") (class "Default")
      (node (ref "A1") (pin "12") (pinfunction "GPIO0_12") (pintype "bidirectional"))
      (node (ref "X11") (pin "4") (pinfunction "4_4") (pintype "passive"))
    )
    (net (code "35") (name "Net-(A1-GPIO2)") (class "Default")
      (node (ref "A1") (pin "11") (pinfunction "GPIO2_11") (pintype "bidirectional"))
      (node (ref "X11") (pin "5") (pinfunction "5_5") (pintype "passive"))
    )
    (net (code "36") (name "Net-(A1-GPIO15)") (class "Default")
      (node (ref "A1") (pin "10") (pinfunction "GPIO15_10") (pintype "bidirectional"))
      (node (ref "R29") (pin "2") (pinfunction "2_2") (pintype "passive"))
    )
    (net (code "37") (name "Net-(A2A-3.3V_100MA)") (class "Default")
      (node (ref "A2") (pin "26") (pinfunction "3.3V_100MA_26") (pintype "bidirectional"))
      (node (ref "V1") (pin "2") (pinfunction "2_2") (pintype "bidirectional"))
    )
    (net (code "38") (name "Net-(A2A-VIN_3.7-5.5V)") (class "Default")
      (node (ref "A2") (pin "28") (pinfunction "VIN_3.7-5.5V_28") (pintype "bidirectional"))
      (node (ref "D1") (pin "C") (pinfunction "C_C") (pintype "passive"))
    )
    (net (code "39") (name "Net-(A2B-A11)") (class "Default")
      (node (ref "A2") (pin "34") (pinfunction "A11_34") (pintype "bidirectional"))
      (node (ref "C26") (pin "1") (pinfunction "1_1") (pintype "passive"))
      (node (ref "R41") (pin "1") (pinfunction "1_1") (pintype "passive"))
      (node (ref "R42") (pin "2") (pinfunction "2_2") (pintype "passive"))
      (node (ref "V1") (pin "3") (pinfunction "3_3") (pintype "bidirectional"))
    )
    (net (code "40") (name "Net-(C20-Pad2)") (class "Default")
      (node (ref "C20") (pin "2") (pinfunction "2_2") (pintype "passive"))
      (node (ref "R40") (pin "2") (pinfunction "2_2") (pintype "passive"))
    )
    (net (code "41") (name "Net-(D2-OA)") (class "Default")
      (node (ref "D2") (pin "1") (pinfunction "OA_1") (pintype "bidirectional"))
      (node (ref "X2") (pin "5") (pinfunction "5_5") (pintype "passive"))
    )
    (net (code "42") (name "Net-(D2-OB)") (class "Default")
      (node (ref "D2") (pin "4") (pinfunction "OB_4") (pintype "bidirectional"))
      (node (ref "X2") (pin "6") (pinfunction "6_6") (pintype "passive"))
    )
    (net (code "43") (name "Net-(D3-OA)") (class "Default")
      (node (ref "D3") (pin "1") (pinfunction "OA_1") (pintype "bidirectional"))
      (node (ref "X1") (pin "1") (pinfunction "1_1") (pintype "passive"))
      (node (ref "X4") (pin "1") (pinfunction "1_1") (pintype "passive"))
    )
    (net (code "44") (name "Net-(D3-OB)") (class "Default")
      (node (ref "D3") (pin "4") (pinfunction "OB_4") (pintype "bidirectional"))
      (node (ref "X1") (pin "2") (pinfunction "2_2") (pintype "passive"))
      (node (ref "X4") (pin "2") (pinfunction "2_2") (pintype "passive"))
    )
    (net (code "45") (name "Net-(D4-OA)") (class "Default")
      (node (ref "D4") (pin "1") (pinfunction "OA_1") (pintype "bidirectional"))
      (node (ref "X2") (pin "7") (pinfunction "7_7") (pintype "passive"))
    )
    (net (code "46") (name "Net-(D4-OB)") (class "Default")
      (node (ref "D4") (pin "4") (pinfunction "OB_4") (pintype "bidirectional"))
      (node (ref "X2") (pin "8") (pinfunction "8_8") (pintype "passive"))
    )
    (net (code "47") (name "Net-(D5-OA)") (class "Default")
      (node (ref "D5") (pin "1") (pinfunction "OA_1") (pintype "bidirectional"))
      (node (ref "X1") (pin "3") (pinfunction "3_3") (pintype "passive"))
      (node (ref "X4") (pin "3") (pinfunction "3_3") (pintype "passive"))
    )
    (net (code "48") (name "Net-(D5-OB)") (class "Default")
      (node (ref "D5") (pin "4") (pinfunction "OB_4") (pintype "bidirectional"))
      (node (ref "X1") (pin "4") (pinfunction "4_4") (pintype "passive"))
      (node (ref "X4") (pin "4") (pinfunction "4_4") (pintype "passive"))
    )
    (net (code "49") (name "Net-(D6-OA)") (class "Default")
      (node (ref "D6") (pin "1") (pinfunction "OA_1") (pintype "bidirectional"))
      (node (ref "X3") (pin "1") (pinfunction "1_1") (pintype "passive"))
      (node (ref "X4") (pin "5") (pinfunction "5_5") (pintype "passive"))
    )
    (net (code "50") (name "Net-(D6-OB)") (class "Default")
      (node (ref "D6") (pin "4") (pinfunction "OB_4") (pintype "bidirectional"))
      (node (ref "X3") (pin "2") (pinfunction "2_2") (pintype "passive"))
      (node (ref "X4") (pin "6") (pinfunction "6_6") (pintype "passive"))
    )
    (net (code "51") (name "Net-(D7-OA)") (class "Default")
      (node (ref "D7") (pin "1") (pinfunction "OA_1") (pintype "bidirectional"))
      (node (ref "X3") (pin "3") (pinfunction "3_3") (pintype "passive"))
      (node (ref "X4") (pin "7") (pinfunction "7_7") (pintype "passive"))
    )
    (net (code "52") (name "Net-(D7-OB)") (class "Default")
      (node (ref "D7") (pin "4") (pinfunction "OB_4") (pintype "bidirectional"))
      (node (ref "X3") (pin "4") (pinfunction "4_4") (pintype "passive"))
      (node (ref "X4") (pin "8") (pinfunction "8_8") (pintype "passive"))
    )
    (net (code "53") (name "Net-(D8-OA)") (class "Default")
      (node (ref "D8") (pin "1") (pinfunction "OA_1") (pintype "bidirectional"))
      (node (ref "K1") (pin "K2") (pinfunction "2_K2") (pintype "passive"))
    )
    (net (code "54") (name "Net-(D8-OB)") (class "Default")
      (node (ref "D8") (pin "4") (pinfunction "OB_4") (pintype "bidirectional"))
      (node (ref "K2") (pin "K2") (pinfunction "2_K2") (pintype "passive"))
    )
    (net (code "55") (name "Net-(D10-GP0)") (class "Default")
      (node (ref "D10") (pin "12") (pinfunction "GP0_12") (pintype "bidirectional"))
      (node (ref "OK1") (pin "4") (pinfunction "COL_4") (pintype "passive"))
      (node (ref "R15") (pin "1") (pinfunction "1_1") (pintype "passive"))
    )
    (net (code "56") (name "Net-(D10-GP1)") (class "Default")
      (node (ref "D10") (pin "13") (pinfunction "GP1_13") (pintype "bidirectional"))
      (node (ref "OK2") (pin "4") (pinfunction "COL_4") (pintype "passive"))
      (node (ref "R14") (pin "1") (pinfunction "1_1") (pintype "passive"))
    )
    (net (code "57") (name "Net-(D10-GP2)") (class "Default")
      (node (ref "D10") (pin "14") (pinfunction "GP2_14") (pintype "bidirectional"))
      (node (ref "OK3") (pin "4") (pinfunction "COL_4") (pintype "passive"))
      (node (ref "R13") (pin "1") (pinfunction "1_1") (pintype "passive"))
    )
    (net (code "58") (name "Net-(D10-GP3)") (class "Default")
      (node (ref "D10") (pin "15") (pinfunction "GP3_15") (pintype "bidirectional"))
      (node (ref "OK4") (pin "4") (pinfunction "COL_4") (pintype "passive"))
      (node (ref "R12") (pin "1") (pinfunction "1_1") (pintype "passive"))
    )
    (net (code "59") (name "Net-(D10-GP4)") (class "Default")
      (node (ref "D10") (pin "16") (pinfunction "GP4_16") (pintype "bidirectional"))
      (node (ref "OK5") (pin "4") (pinfunction "COL_4") (pintype "passive"))
      (node (ref "R11") (pin "1") (pinfunction "1_1") (pintype "passive"))
    )
    (net (code "60") (name "Net-(D10-GP5)") (class "Default")
      (node (ref "D10") (pin "17") (pinfunction "GP5_17") (pintype "bidirectional"))
      (node (ref "OK6") (pin "4") (pinfunction "COL_4") (pintype "passive"))
      (node (ref "R10") (pin "1") (pinfunction "1_1") (pintype "passive"))
    )
    (net (code "61") (name "Net-(K1B-O)") (class "Default")
      (node (ref "K1") (pin "NC") (pinfunction "O_NC") (pintype "passive"))
      (node (ref "X5") (pin "1") (pinfunction "1_1") (pintype "passive"))
    )
    (net (code "62") (name "Net-(K1B-P)") (class "Default")
      (node (ref "K1") (pin "COM") (pinfunction "P_COM") (pintype "passive"))
      (node (ref "X5") (pin "2") (pinfunction "2_2") (pintype "passive"))
      (node (ref "X5") (pin "3") (pinfunction "3_3") (pintype "passive"))
    )
    (net (code "63") (name "Net-(K1B-S)") (class "Default")
      (node (ref "K1") (pin "NO") (pinfunction "S_NO") (pintype "passive"))
      (node (ref "X5") (pin "4") (pinfunction "4_4") (pintype "passive"))
    )
    (net (code "64") (name "Net-(K2B-O)") (class "Default")
      (node (ref "K2") (pin "NC") (pinfunction "O_NC") (pintype "passive"))
      (node (ref "X5") (pin "5") (pinfunction "5_5") (pintype "passive"))
    )
    (net (code "65") (name "Net-(K2B-P)") (class "Default")
      (node (ref "K2") (pin "COM") (pinfunction "P_COM") (pintype "passive"))
      (node (ref "X5") (pin "6") (pinfunction "6_6") (pintype "passive"))
      (node (ref "X5") (pin "7") (pinfunction "7_7") (pintype "passive"))
    )
    (net (code "66") (name "Net-(K2B-S)") (class "Default")
      (node (ref "K2") (pin "NO") (pinfunction "S_NO") (pintype "passive"))
      (node (ref "X5") (pin "8") (pinfunction "8_8") (pintype "passive"))
    )
    (net (code "67") (name "Net-(N1-BIAS)") (class "Default")
      (node (ref "N1") (pin "1") (pinfunction "BIAS_1") (pintype "bidirectional"))
      (node (ref "N1") (pin "2") (pinfunction "REFIN+_2") (pintype "bidirectional"))
      (node (ref "R1") (pin "2") (pinfunction "2_2") (pintype "passive"))
    )
    (net (code "68") (name "Net-(N1-FORCE+)") (class "Default")
      (node (ref "C1") (pin "1") (pinfunction "1_1") (pintype "passive"))
      (node (ref "N1") (pin "5") (pinfunction "FORCE+_5") (pintype "bidirectional"))
      (node (ref "N1") (pin "7") (pinfunction "RTDIN+_7") (pintype "bidirectional"))
      (node (ref "X10") (pin "1") (pinfunction "1_1") (pintype "passive"))
    )
    (net (code "69") (name "Net-(N1-FORCE-)") (class "Default")
      (node (ref "C1") (pin "2") (pinfunction "2_2") (pintype "passive"))
      (node (ref "N1") (pin "8") (pinfunction "RTDIN-_8") (pintype "bidirectional"))
      (node (ref "N1") (pin "9") (pinfunction "FORCE-_9") (pintype "bidirectional"))
      (node (ref "X10") (pin "2") (pinfunction "2_2") (pintype "passive"))
    )
    (net (code "70") (name "Net-(N1-ISENSOR)") (class "Default")
      (node (ref "N1") (pin "3") (pinfunction "REFIN-_3") (pintype "bidirectional"))
      (node (ref "N1") (pin "4") (pinfunction "ISENSOR_4") (pintype "bidirectional"))
      (node (ref "R1") (pin "1") (pinfunction "1_1") (pintype "passive"))
    )
    (net (code "71") (name "Net-(N3-BOOT)") (class "Default")
      (node (ref "C18") (pin "2") (pinfunction "2_2") (pintype "passive"))
      (node (ref "N3") (pin "1") (pinfunction "BOOT_1") (pintype "bidirectional"))
    )
    (net (code "72") (name "Net-(N3-PH)") (class "Default")
      (node (ref "C18") (pin "1") (pinfunction "1_1") (pintype "passive"))
      (node (ref "D9") (pin "C") (pinfunction "C_C") (pintype "passive"))
      (node (ref "L2") (pin "1") (pinfunction "1_1") (pintype "passive"))
      (node (ref "N3") (pin "8") (pinfunction "PH_8") (pintype "bidirectional"))
    )
    (net (code "73") (name "Net-(N3-SENSE)") (class "Default")
      (node (ref "C19") (pin "1") (pinfunction "1_1") (pintype "passive"))
      (node (ref "C20") (pin "1") (pinfunction "1_1") (pintype "passive"))
      (node (ref "N3") (pin "4") (pinfunction "SENSE_4") (pintype "bidirectional"))
      (node (ref "R38") (pin "1") (pinfunction "1_1") (pintype "passive"))
      (node (ref "R39") (pin "2") (pinfunction "2_2") (pintype "passive"))
    )
    (net (code "74") (name "Net-(OK1-A)") (class "Default")
      (node (ref "OK1") (pin "1") (pinfunction "A_1") (pintype "passive"))
      (node (ref "R8") (pin "2") (pinfunction "2_2") (pintype "passive"))
    )
    (net (code "75") (name "Net-(OK1-C)") (class "Default")
      (node (ref "OK1") (pin "2") (pinfunction "C_2") (pintype "passive"))
      (node (ref "OK2") (pin "2") (pinfunction "C_2") (pintype "passive"))
      (node (ref "OK3") (pin "2") (pinfunction "C_2") (pintype "passive"))
      (node (ref "X6") (pin "8") (pinfunction "8_8") (pintype "passive"))
    )
    (net (code "76") (name "Net-(OK2-A)") (class "Default")
      (node (ref "OK2") (pin "1") (pinfunction "A_1") (pintype "passive"))
      (node (ref "R7") (pin "2") (pinfunction "2_2") (pintype "passive"))
    )
    (net (code "77") (name "Net-(OK3-A)") (class "Default")
      (node (ref "OK3") (pin "1") (pinfunction "A_1") (pintype "passive"))
      (node (ref "R6") (pin "2") (pinfunction "2_2") (pintype "passive"))
    )
    (net (code "78") (name "Net-(OK4-A)") (class "Default")
      (node (ref "OK4") (pin "1") (pinfunction "A_1") (pintype "passive"))
      (node (ref "R5") (pin "2") (pinfunction "2_2") (pintype "passive"))
    )
    (net (code "79") (name "Net-(OK4-C)") (class "Default")
      (node (ref "OK4") (pin "2") (pinfunction "C_2") (pintype "passive"))
      (node (ref "OK5") (pin "2") (pinfunction "C_2") (pintype "passive"))
      (node (ref "OK6") (pin "2") (pinfunction "C_2") (pintype "passive"))
      (node (ref "X7") (pin "8") (pinfunction "8_8") (pintype "passive"))
    )
    (net (code "80") (name "Net-(OK5-A)") (class "Default")
      (node (ref "OK5") (pin "1") (pinfunction "A_1") (pintype "passive"))
      (node (ref "R4") (pin "2") (pinfunction "2_2") (pintype "passive"))
    )
    (net (code "81") (name "Net-(OK6-A)") (class "Default")
      (node (ref "OK6") (pin "1") (pinfunction "A_1") (pintype "passive"))
      (node (ref "R3") (pin "2") (pinfunction "2_2") (pintype "passive"))
    )
    (net (code "82") (name "Net-(R3-Pad1)") (class "Default")
      (node (ref "R3") (pin "1") (pinfunction "1_1") (pintype "passive"))
      (node (ref "X7") (pin "7") (pinfunction "7_7") (pintype "passive"))
    )
    (net (code "83") (name "Net-(R4-Pad1)") (class "Default")
      (node (ref "R4") (pin "1") (pinfunction "1_1") (pintype "passive"))
      (node (ref "X7") (pin "5") (pinfunction "5_5") (pintype "passive"))
    )
    (net (code "84") (name "Net-(R5-Pad1)") (class "Default")
      (node (ref "R5") (pin "1") (pinfunction "1_1") (pintype "passive"))
      (node (ref "X7") (pin "3") (pinfunction "3_3") (pintype "passive"))
    )
    (net (code "85") (name "Net-(R6-Pad1)") (class "Default")
      (node (ref "R6") (pin "1") (pinfunction "1_1") (pintype "passive"))
      (node (ref "X6") (pin "7") (pinfunction "7_7") (pintype "passive"))
    )
    (net (code "86") (name "Net-(R7-Pad1)") (class "Default")
      (node (ref "R7") (pin "1") (pinfunction "1_1") (pintype "passive"))
      (node (ref "X6") (pin "5") (pinfunction "5_5") (pintype "passive"))
    )
    (net (code "87") (name "Net-(R8-Pad1)") (class "Default")
      (node (ref "R8") (pin "1") (pinfunction "1_1") (pintype "passive"))
      (node (ref "X6") (pin "3") (pinfunction "3_3") (pintype "passive"))
    )
    (net (code "88") (name "Net-(X6-Pad1)") (class "Default")
      (node (ref "X6") (pin "1") (pinfunction "1_1") (pintype "passive"))
      (node (ref "X6") (pin "2") (pinfunction "2_2") (pintype "passive"))
      (node (ref "X6") (pin "4") (pinfunction "4_4") (pintype "passive"))
      (node (ref "X6") (pin "6") (pinfunction "6_6") (pintype "passive"))
    )
    (net (code "89") (name "Net-(X7-Pad1)") (class "Default")
      (node (ref "X7") (pin "1") (pinfunction "1_1") (pintype "passive"))
      (node (ref "X7") (pin "2") (pinfunction "2_2") (pintype "passive"))
      (node (ref "X7") (pin "4") (pinfunction "4_4") (pintype "passive"))
      (node (ref "X7") (pin "6") (pinfunction "6_6") (pintype "passive"))
    )
    (net (code "90") (name "unconnected-(A1-ADC-Pad2)") (class "Default")
      (node (ref "A1") (pin "2") (pinfunction "ADC_2") (pintype "bidirectional"))
    )
    (net (code "91") (name "unconnected-(A1-GPIO4-Pad14)") (class "Default")
      (node (ref "A1") (pin "14") (pinfunction "GPIO4_14") (pintype "bidirectional"))
    )
    (net (code "92") (name "unconnected-(A1-GPIO5-Pad13)") (class "Default")
      (node (ref "A1") (pin "13") (pinfunction "GPIO5_13") (pintype "bidirectional"))
    )
    (net (code "93") (name "unconnected-(A1-GPIO12-Pad6)") (class "Default")
      (node (ref "A1") (pin "6") (pinfunction "GPIO12_6") (pintype "bidirectional"))
    )
    (net (code "94") (name "unconnected-(A1-GPIO13-Pad7)") (class "Default")
      (node (ref "A1") (pin "7") (pinfunction "GPIO13_7") (pintype "bidirectional"))
    )
    (net (code "95") (name "unconnected-(A1-GPIO14-Pad5)") (class "Default")
      (node (ref "A1") (pin "5") (pinfunction "GPIO14_5") (pintype "bidirectional"))
    )
    (net (code "96") (name "unconnected-(A1-GPIO16-Pad4)") (class "Default")
      (node (ref "A1") (pin "4") (pinfunction "GPIO16_4") (pintype "bidirectional"))
    )
    (net (code "97") (name "unconnected-(A2B-3.3V-Pad32)") (class "Default")
      (node (ref "A2") (pin "32") (pinfunction "3.3V_32") (pintype "bidirectional"))
    )
    (net (code "98") (name "unconnected-(A2B-A10-Pad35)") (class "Default")
      (node (ref "A2") (pin "35") (pinfunction "A10_35") (pintype "bidirectional"))
    )
    (net (code "99") (name "unconnected-(A2B-A14{slash}DAC-Pad29)") (class "Default")
      (node (ref "A2") (pin "29") (pinfunction "A14/DAC_29") (pintype "bidirectional"))
    )
    (net (code "100") (name "unconnected-(A2B-AREF-Pad36)") (class "Default")
      (node (ref "A2") (pin "36") (pinfunction "AREF_36") (pintype "bidirectional"))
    )
    (net (code "101") (name "unconnected-(A2B-PROG-Pad30)") (class "Default")
      (node (ref "A2") (pin "30") (pinfunction "PROG_30") (pintype "bidirectional"))
    )
    (net (code "102") (name "unconnected-(A2B-VBAT-Pad33)") (class "Default")
      (node (ref "A2") (pin "33") (pinfunction "VBAT_33") (pintype "bidirectional"))
    )
    (net (code "103") (name "unconnected-(A2B-VUSB-Pad37)") (class "Default")
      (node (ref "A2") (pin "37") (pinfunction "VUSB_37") (pintype "bidirectional"))
    )
    (net (code "104") (name "unconnected-(N1-N.C.-Pad17)") (class "Default")
      (node (ref "N1") (pin "17") (pinfunction "N.C._17") (pintype "bidirectional"))
    )
    (net (code "105") (name "unconnected-(X1-Pad5)") (class "Default")
      (node (ref "X1") (pin "5") (pinfunction "5_5") (pintype "passive"))
    )
    (net (code "106") (name "unconnected-(X3-Pad5)") (class "Default")
      (node (ref "X3") (pin "5") (pinfunction "5_5") (pintype "passive"))
    )
    (net (code "107") (name "unconnected-(X9-Pad7)") (class "Default")
      (node (ref "X9") (pin "7") (pinfunction "7_7") (pintype "passive"))
    )
  )
)
